# TOF_Sensor_Unit_v02_single.net
KiCad netlist of a schematic drawn in EasyEDA Pro
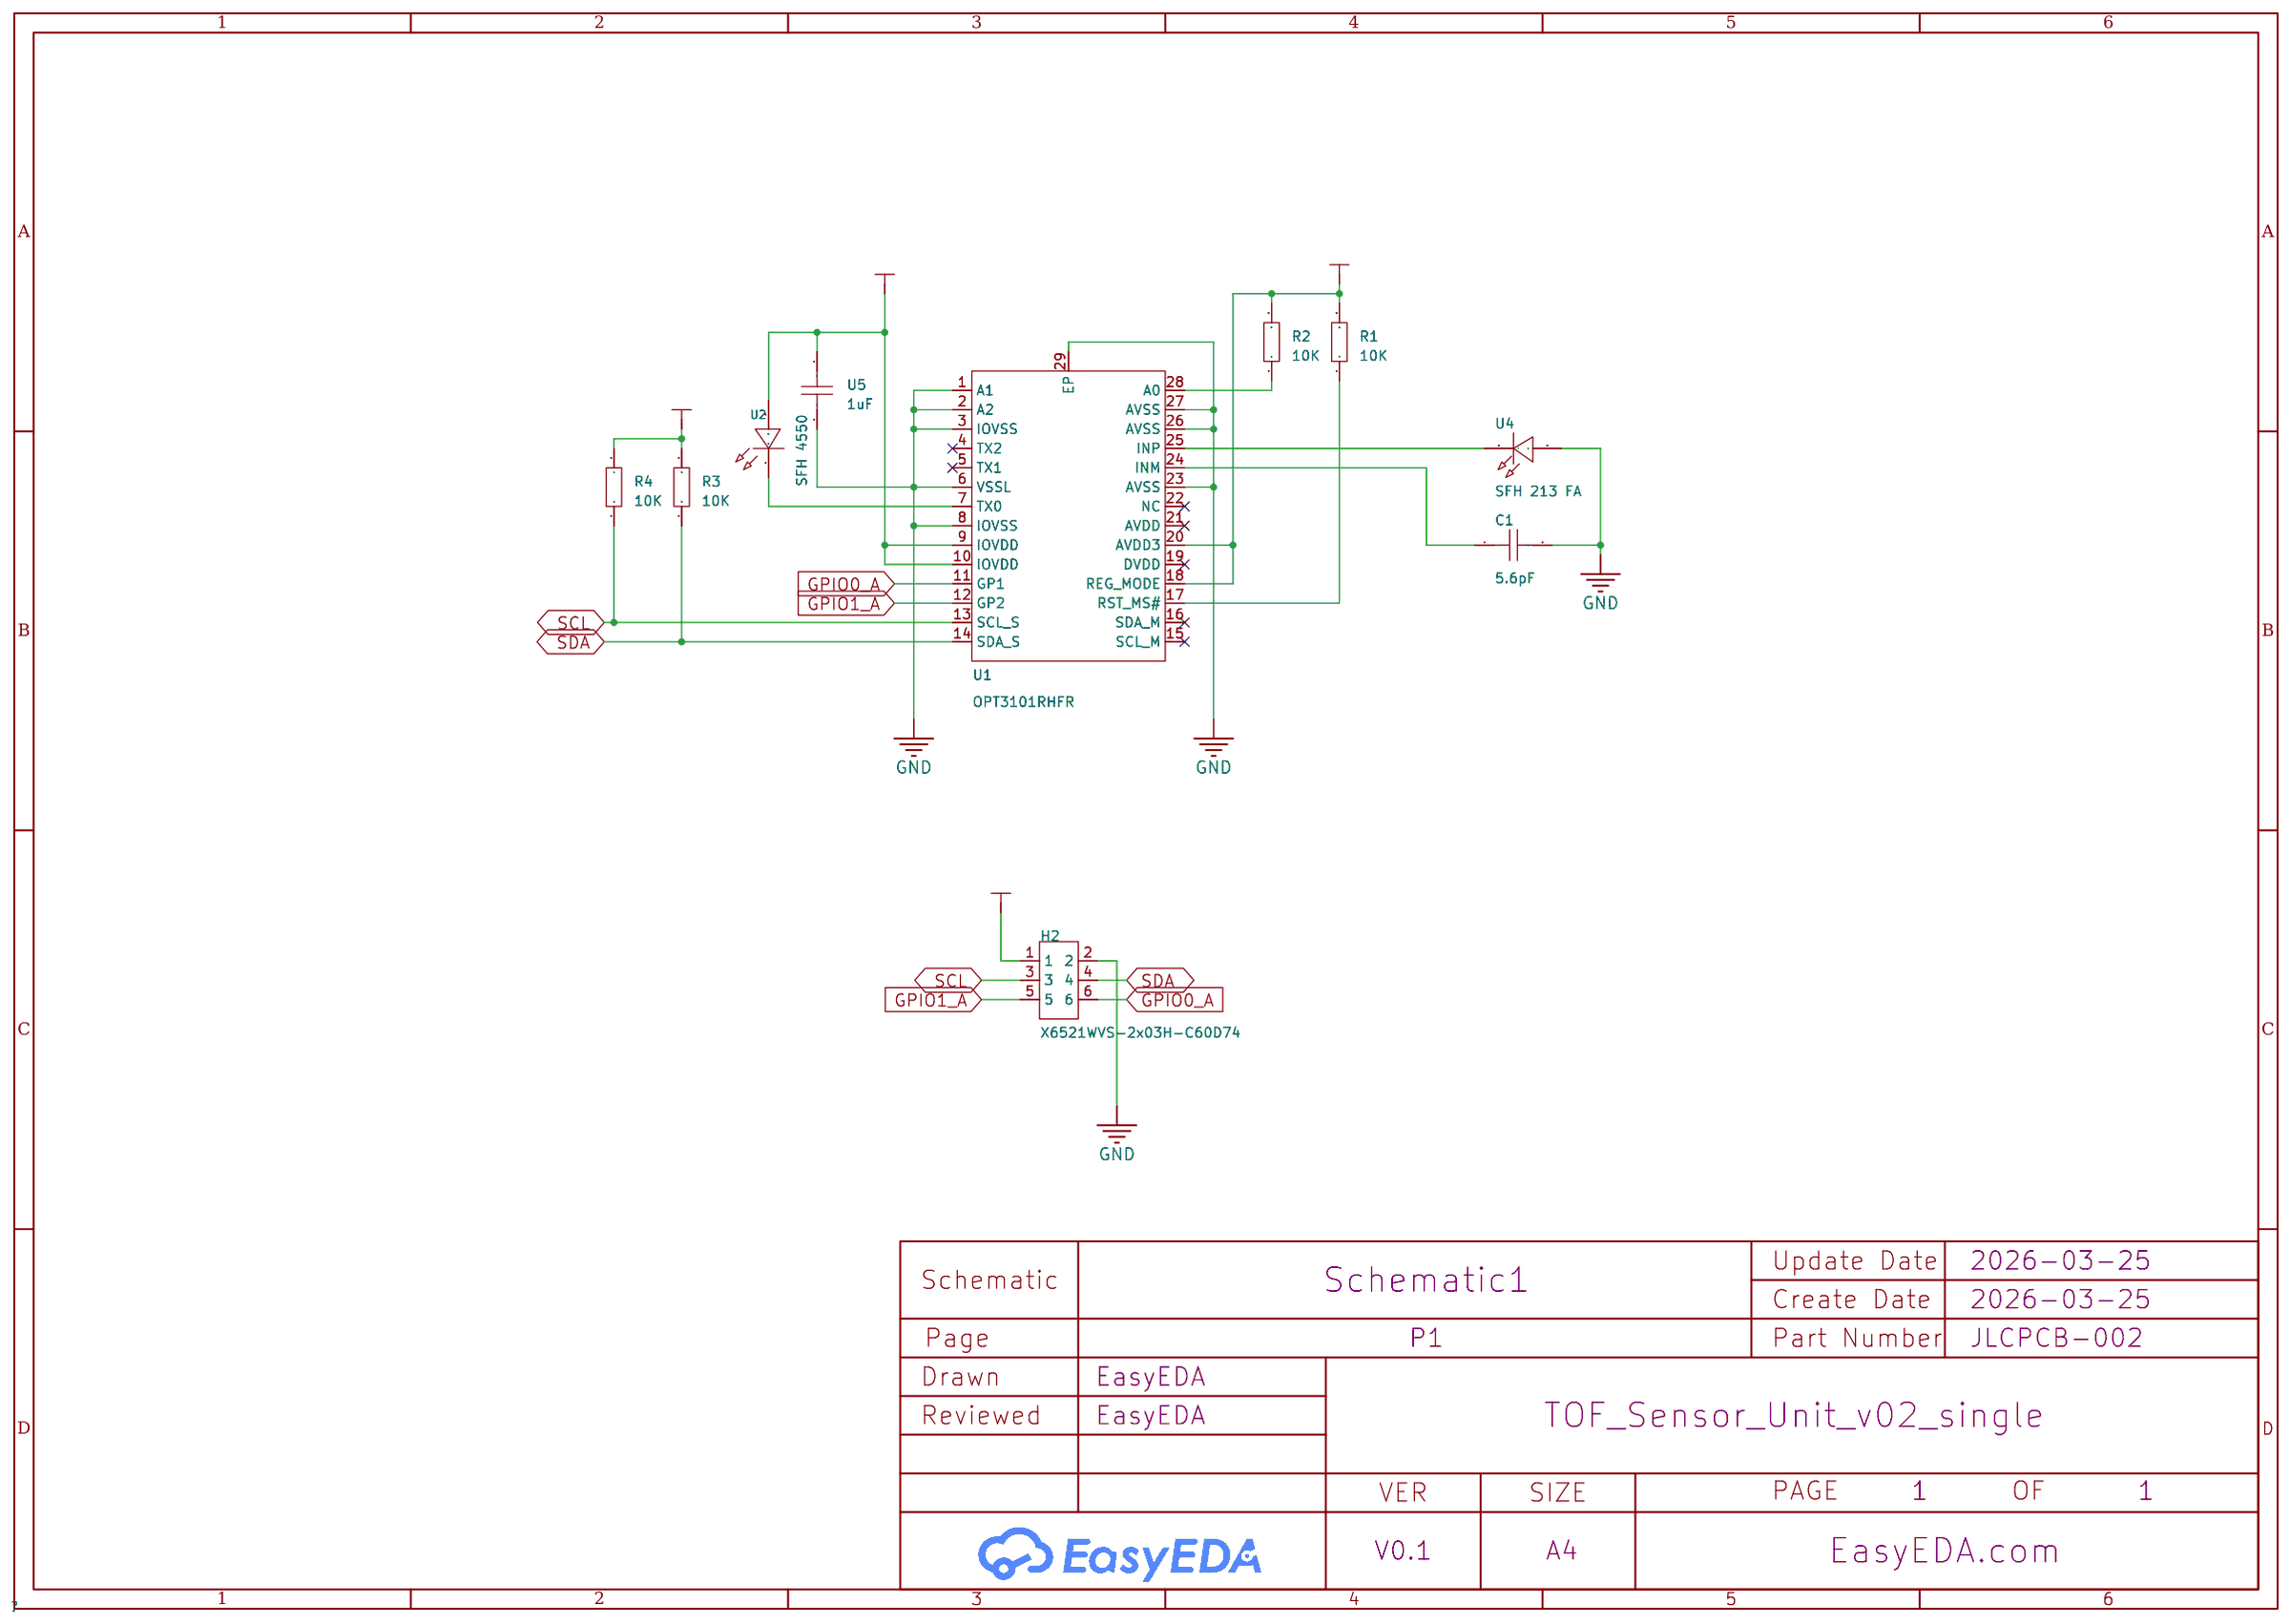
[diagram p0: schematic sheet]

(export (version "E")
  (design (tool "Eeschema 10.0.6"))
  (components
    (comp (ref "C1")
      (value "5.6pF")
      (footprint "easyedapro:C0402")
      (description "Capacitance:5.6pF Voltage Rating:50V Temperature Coefficient:NP0")
      (fields
        (field (name "Manufacturer Part") "CC0402BRNPO9BN5R6")
        (field (name "Manufacturer") "YAGEO(国巨)")
      )
      (libsource (lib "easyedapro") (part "CC0402BRNPO9BN5R6"))
    )
    (comp (ref "H2")
      (value "X6521WVS-2x03H-C60D74")
      (footprint "easyedapro:HDR-SMD_6P-P2.54-V-M-R2-C5-S7.4")
      (fields (field (name "Manufacturer") "XKB Connection(中国星坤)"))
      (libsource (lib "easyedapro") (part "X6521WVS-2*03H-C60D74"))
    )
    (comp (ref "R1")
      (value "10K")
      (footprint "easyedapro:R0603")
      (description "DNI")
      (libsource (lib "easyedapro") (part "Res"))
    )
    (comp (ref "R2")
      (value "10K")
      (footprint "easyedapro:R0603")
      (description "DNI")
      (libsource (lib "easyedapro") (part "Res"))
    )
    (comp (ref "R3")
      (value "10K")
      (footprint "easyedapro:R0603")
      (description "DNI")
      (libsource (lib "easyedapro") (part "Res"))
    )
    (comp (ref "R4")
      (value "10K")
      (footprint "easyedapro:R0603")
      (description "DNI")
      (libsource (lib "easyedapro") (part "Res"))
    )
    (comp (ref "U1")
      (value "OPT3101RHFR")
      (footprint "easyedapro:QFN-28_L5.0-W4.0-P0.50-BL-EP")
      (fields (field (name "Manufacturer") "TI(德州仪器)"))
      (libsource (lib "easyedapro") (part "OPT3101RHFR"))
    )
    (comp (ref "U2")
      (value "SFH 4550")
      (footprint "easyedapro:LED-TH_BD5.9-P2.54-RD")
      (fields (field (name "Manufacturer") "OSRAM(欧司朗)"))
      (libsource (lib "easyedapro") (part "SFH 4550"))
    )
    (comp (ref "U4")
      (value "SFH 213 FA")
      (footprint "easyedapro:OPTO-TH_BD5.8-P2.54-R-FD")
      (fields (field (name "Manufacturer") "OSRAM(欧司朗)"))
      (libsource (lib "easyedapro") (part "SFH 213 FA"))
    )
    (comp (ref "U5")
      (value "1uF")
      (footprint "easyedapro:C0402")
      (description "Capacitance:1uF Tolerance:±10% Tolerance:±10% Voltage Rating:10V Temperature Coefficient:X5R")
      (fields
        (field (name "Manufacturer Part") "CGA0402X5R105K100GT")
        (field (name "Manufacturer") "HRE(芯声)")
      )
      (libsource (lib "easyedapro") (part "CGA0402X5R105K100GT"))
    )
  )
  (nets
    (net (code "1") (name "3V3") (class "Default")
      (node (ref "H2") (pin "1") (pinfunction "1_1") (pintype "unspecified"))
      (node (ref "R1") (pin "2") (pinfunction "2_2") (pintype "input"))
      (node (ref "R2") (pin "2") (pinfunction "2_2") (pintype "input"))
      (node (ref "R3") (pin "2") (pinfunction "2_2") (pintype "input"))
      (node (ref "R4") (pin "2") (pinfunction "2_2") (pintype "input"))
      (node (ref "U1") (pin "10") (pinfunction "IOVDD_10") (pintype "unspecified"))
      (node (ref "U1") (pin "18") (pinfunction "REG_MODE_18") (pintype "unspecified"))
      (node (ref "U1") (pin "20") (pinfunction "AVDD3_20") (pintype "unspecified"))
      (node (ref "U1") (pin "9") (pinfunction "IOVDD_9") (pintype "unspecified"))
      (node (ref "U2") (pin "2") (pinfunction "2_2") (pintype "input"))
      (node (ref "U5") (pin "1") (pinfunction "1_1") (pintype "unspecified"))
    )
    (net (code "2") (name "GND") (class "Default")
      (node (ref "C1") (pin "2") (pinfunction "2_2") (pintype "unspecified"))
      (node (ref "H2") (pin "2") (pinfunction "2_2") (pintype "unspecified"))
      (node (ref "U1") (pin "1") (pinfunction "A1_1") (pintype "unspecified"))
      (node (ref "U1") (pin "2") (pinfunction "A2_2") (pintype "unspecified"))
      (node (ref "U1") (pin "23") (pinfunction "AVSS_23") (pintype "unspecified"))
      (node (ref "U1") (pin "26") (pinfunction "AVSS_26") (pintype "unspecified"))
      (node (ref "U1") (pin "27") (pinfunction "AVSS_27") (pintype "unspecified"))
      (node (ref "U1") (pin "29") (pinfunction "EP_29") (pintype "unspecified"))
      (node (ref "U1") (pin "3") (pinfunction "IOVSS_3") (pintype "unspecified"))
      (node (ref "U1") (pin "6") (pinfunction "VSSL_6") (pintype "unspecified"))
      (node (ref "U1") (pin "8") (pinfunction "IOVSS_8") (pintype "unspecified"))
      (node (ref "U4") (pin "2") (pinfunction "+_2") (pintype "unspecified"))
      (node (ref "U5") (pin "2") (pinfunction "2_2") (pintype "unspecified"))
    )
    (net (code "3") (name "GPIO0_A") (class "Default")
      (node (ref "H2") (pin "6") (pinfunction "6_6") (pintype "unspecified"))
      (node (ref "U1") (pin "11") (pinfunction "GP1_11") (pintype "unspecified"))
    )
    (net (code "4") (name "GPIO1_A") (class "Default")
      (node (ref "H2") (pin "5") (pinfunction "5_5") (pintype "unspecified"))
      (node (ref "U1") (pin "12") (pinfunction "GP2_12") (pintype "unspecified"))
    )
    (net (code "5") (name "Net-(U1-A0)") (class "Default")
      (node (ref "R2") (pin "1") (pinfunction "1_1") (pintype "input"))
      (node (ref "U1") (pin "28") (pinfunction "A0_28") (pintype "unspecified"))
    )
    (net (code "6") (name "Net-(U1-INM)") (class "Default")
      (node (ref "C1") (pin "1") (pinfunction "1_1") (pintype "unspecified"))
      (node (ref "U1") (pin "24") (pinfunction "INM_24") (pintype "unspecified"))
    )
    (net (code "7") (name "Net-(U1-INP)") (class "Default")
      (node (ref "U1") (pin "25") (pinfunction "INP_25") (pintype "unspecified"))
      (node (ref "U4") (pin "1") (pinfunction "-_1") (pintype "unspecified"))
    )
    (net (code "8") (name "Net-(U1-RST_MS#)") (class "Default")
      (node (ref "R1") (pin "1") (pinfunction "1_1") (pintype "input"))
      (node (ref "U1") (pin "17") (pinfunction "RST_MS#_17") (pintype "unspecified"))
    )
    (net (code "9") (name "Net-(U1-TX0)") (class "Default")
      (node (ref "U1") (pin "7") (pinfunction "TX0_7") (pintype "unspecified"))
      (node (ref "U2") (pin "1") (pinfunction "1_1") (pintype "input"))
    )
    (net (code "10") (name "SCL") (class "Default")
      (node (ref "H2") (pin "3") (pinfunction "3_3") (pintype "unspecified"))
      (node (ref "R4") (pin "1") (pinfunction "1_1") (pintype "input"))
      (node (ref "U1") (pin "13") (pinfunction "SCL_S_13") (pintype "unspecified"))
    )
    (net (code "11") (name "SDA") (class "Default")
      (node (ref "H2") (pin "4") (pinfunction "4_4") (pintype "unspecified"))
      (node (ref "R3") (pin "1") (pinfunction "1_1") (pintype "input"))
      (node (ref "U1") (pin "14") (pinfunction "SDA_S_14") (pintype "unspecified"))
    )
    (net (code "12") (name "unconnected-(U1-AVDD-Pad21)") (class "Default")
      (node (ref "U1") (pin "21") (pinfunction "AVDD_21") (pintype "unspecified+no_connect"))
    )
    (net (code "13") (name "unconnected-(U1-DVDD-Pad19)") (class "Default")
      (node (ref "U1") (pin "19") (pinfunction "DVDD_19") (pintype "unspecified+no_connect"))
    )
    (net (code "14") (name "unconnected-(U1-NC-Pad22)") (class "Default")
      (node (ref "U1") (pin "22") (pinfunction "NC_22") (pintype "unspecified+no_connect"))
    )
    (net (code "15") (name "unconnected-(U1-SCL_M-Pad15)") (class "Default")
      (node (ref "U1") (pin "15") (pinfunction "SCL_M_15") (pintype "unspecified+no_connect"))
    )
    (net (code "16") (name "unconnected-(U1-SDA_M-Pad16)") (class "Default")
      (node (ref "U1") (pin "16") (pinfunction "SDA_M_16") (pintype "unspecified+no_connect"))
    )
    (net (code "17") (name "unconnected-(U1-TX1-Pad5)") (class "Default")
      (node (ref "U1") (pin "5") (pinfunction "TX1_5") (pintype "unspecified+no_connect"))
    )
    (net (code "18") (name "unconnected-(U1-TX2-Pad4)") (class "Default")
      (node (ref "U1") (pin "4") (pinfunction "TX2_4") (pintype "unspecified+no_connect"))
    )
  )
)
